# L293D.net
KiCad netlist of a schematic drawn in Altium Designer
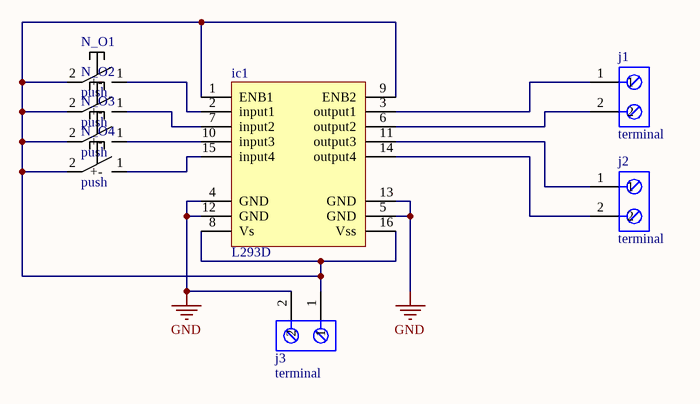
[diagram p0: L293D.SchDoc]

(export (version "E")
  (design (tool "Eeschema 10.0.6"))
  (components
    (comp (ref "ic1")
      (value "L293D")
      (footprint "L293D")
      (description "Half Bridge Based Peripheral Driver, 1.2A, PDIP16")
      (fields (field (name "MANUFACTURER") "STMicroelectronics"))
      (libsource (lib "my schematics") (part "L293D"))
    )
    (comp (ref "j1")
      (value "terminal")
      (footprint "terminal")
      (description "Barrier Strip Terminal Block")
      (fields
        (field (name "MANUFACTURER") "Wurth Electronics")
        (field (name "MANUFACTURER PART NUMBER") "691137710002")
      )
      (libsource (lib "my schematics") (part "691137710002"))
    )
    (comp (ref "j2")
      (value "terminal")
      (footprint "terminal")
      (description "Barrier Strip Terminal Block")
      (fields
        (field (name "MANUFACTURER") "Wurth Electronics")
        (field (name "MANUFACTURER PART NUMBER") "691137710002")
      )
      (libsource (lib "my schematics") (part "691137710002"))
    )
    (comp (ref "j3")
      (value "terminal")
      (footprint "terminal")
      (description "Barrier Strip Terminal Block")
      (fields
        (field (name "MANUFACTURER") "Wurth Electronics")
        (field (name "MANUFACTURER PART NUMBER") "691137710002")
      )
      (libsource (lib "my schematics") (part "691137710002"))
    )
    (comp (ref "N_O1")
      (value "push")
      (footprint "PUSH_BUTTON")
      (description "Pushbutton Switch")
      (fields
        (field (name "MANUFACTURER") "E-Switch")
        (field (name "MANUFACTURER PART NUMBER") "800CSP1B6M2QE")
      )
      (libsource (lib "my schematics") (part "800CSP1B6M2QE"))
    )
    (comp (ref "N_O2")
      (value "push")
      (footprint "PUSH_BUTTON")
      (description "Pushbutton Switch")
      (fields
        (field (name "MANUFACTURER") "E-Switch")
        (field (name "MANUFACTURER PART NUMBER") "800CSP1B6M2QE")
      )
      (libsource (lib "my schematics") (part "800CSP1B6M2QE"))
    )
    (comp (ref "N_O3")
      (value "push")
      (footprint "PUSH_BUTTON")
      (description "Pushbutton Switch")
      (fields
        (field (name "MANUFACTURER") "E-Switch")
        (field (name "MANUFACTURER PART NUMBER") "800CSP1B6M2QE")
      )
      (libsource (lib "my schematics") (part "800CSP1B6M2QE"))
    )
    (comp (ref "N_O4")
      (value "push")
      (footprint "PUSH_BUTTON")
      (description "Pushbutton Switch")
      (fields
        (field (name "MANUFACTURER") "E-Switch")
        (field (name "MANUFACTURER PART NUMBER") "800CSP1B6M2QE")
      )
      (libsource (lib "my schematics") (part "800CSP1B6M2QE"))
    )
  )
  (nets
    (net (code "1") (name "GND") (class "Default")
      (node (ref "ic1") (pin "12") (pinfunction "GND_12") (pintype "passive"))
      (node (ref "ic1") (pin "13") (pinfunction "GND_13") (pintype "passive"))
      (node (ref "ic1") (pin "4") (pinfunction "GND_4") (pintype "passive"))
      (node (ref "ic1") (pin "5") (pinfunction "GND_5") (pintype "passive"))
      (node (ref "j3") (pin "2") (pinfunction "2_2") (pintype "passive"))
    )
    (net (code "2") (name "Net-(N_O1-+)") (class "Default")
      (node (ref "N_O1") (pin "2") (pinfunction "+_2") (pintype "passive"))
      (node (ref "N_O2") (pin "2") (pinfunction "+_2") (pintype "passive"))
      (node (ref "N_O3") (pin "2") (pinfunction "+_2") (pintype "passive"))
      (node (ref "N_O4") (pin "2") (pinfunction "+_2") (pintype "passive"))
      (node (ref "ic1") (pin "1") (pinfunction "ENB1_1") (pintype "passive"))
      (node (ref "ic1") (pin "16") (pinfunction "Vss_16") (pintype "passive"))
      (node (ref "ic1") (pin "8") (pinfunction "Vs_8") (pintype "passive"))
      (node (ref "ic1") (pin "9") (pinfunction "ENB2_9") (pintype "passive"))
      (node (ref "j3") (pin "1") (pinfunction "1_1") (pintype "passive"))
    )
    (net (code "3") (name "Net-(N_O1--)") (class "Default")
      (node (ref "N_O1") (pin "1") (pinfunction "-_1") (pintype "passive"))
      (node (ref "ic1") (pin "2") (pinfunction "input1_2") (pintype "passive"))
    )
    (net (code "4") (name "Net-(N_O2--)") (class "Default")
      (node (ref "N_O2") (pin "1") (pinfunction "-_1") (pintype "passive"))
      (node (ref "ic1") (pin "7") (pinfunction "input2_7") (pintype "passive"))
    )
    (net (code "5") (name "Net-(N_O3--)") (class "Default")
      (node (ref "N_O3") (pin "1") (pinfunction "-_1") (pintype "passive"))
      (node (ref "ic1") (pin "10") (pinfunction "input3_10") (pintype "passive"))
    )
    (net (code "6") (name "Net-(N_O4--)") (class "Default")
      (node (ref "N_O4") (pin "1") (pinfunction "-_1") (pintype "passive"))
      (node (ref "ic1") (pin "15") (pinfunction "input4_15") (pintype "passive"))
    )
    (net (code "7") (name "Net-(ic1-output1)") (class "Default")
      (node (ref "ic1") (pin "3") (pinfunction "output1_3") (pintype "passive"))
      (node (ref "j1") (pin "1") (pinfunction "1_1") (pintype "passive"))
    )
    (net (code "8") (name "Net-(ic1-output2)") (class "Default")
      (node (ref "ic1") (pin "6") (pinfunction "output2_6") (pintype "passive"))
      (node (ref "j1") (pin "2") (pinfunction "2_2") (pintype "passive"))
    )
    (net (code "9") (name "Net-(ic1-output3)") (class "Default")
      (node (ref "ic1") (pin "11") (pinfunction "output3_11") (pintype "passive"))
      (node (ref "j2") (pin "1") (pinfunction "1_1") (pintype "passive"))
    )
    (net (code "10") (name "Net-(ic1-output4)") (class "Default")
      (node (ref "ic1") (pin "14") (pinfunction "output4_14") (pintype "passive"))
      (node (ref "j2") (pin "2") (pinfunction "2_2") (pintype "passive"))
    )
  )
)
